# CPU.net
KiCad netlist of a schematic drawn in Altium Designer
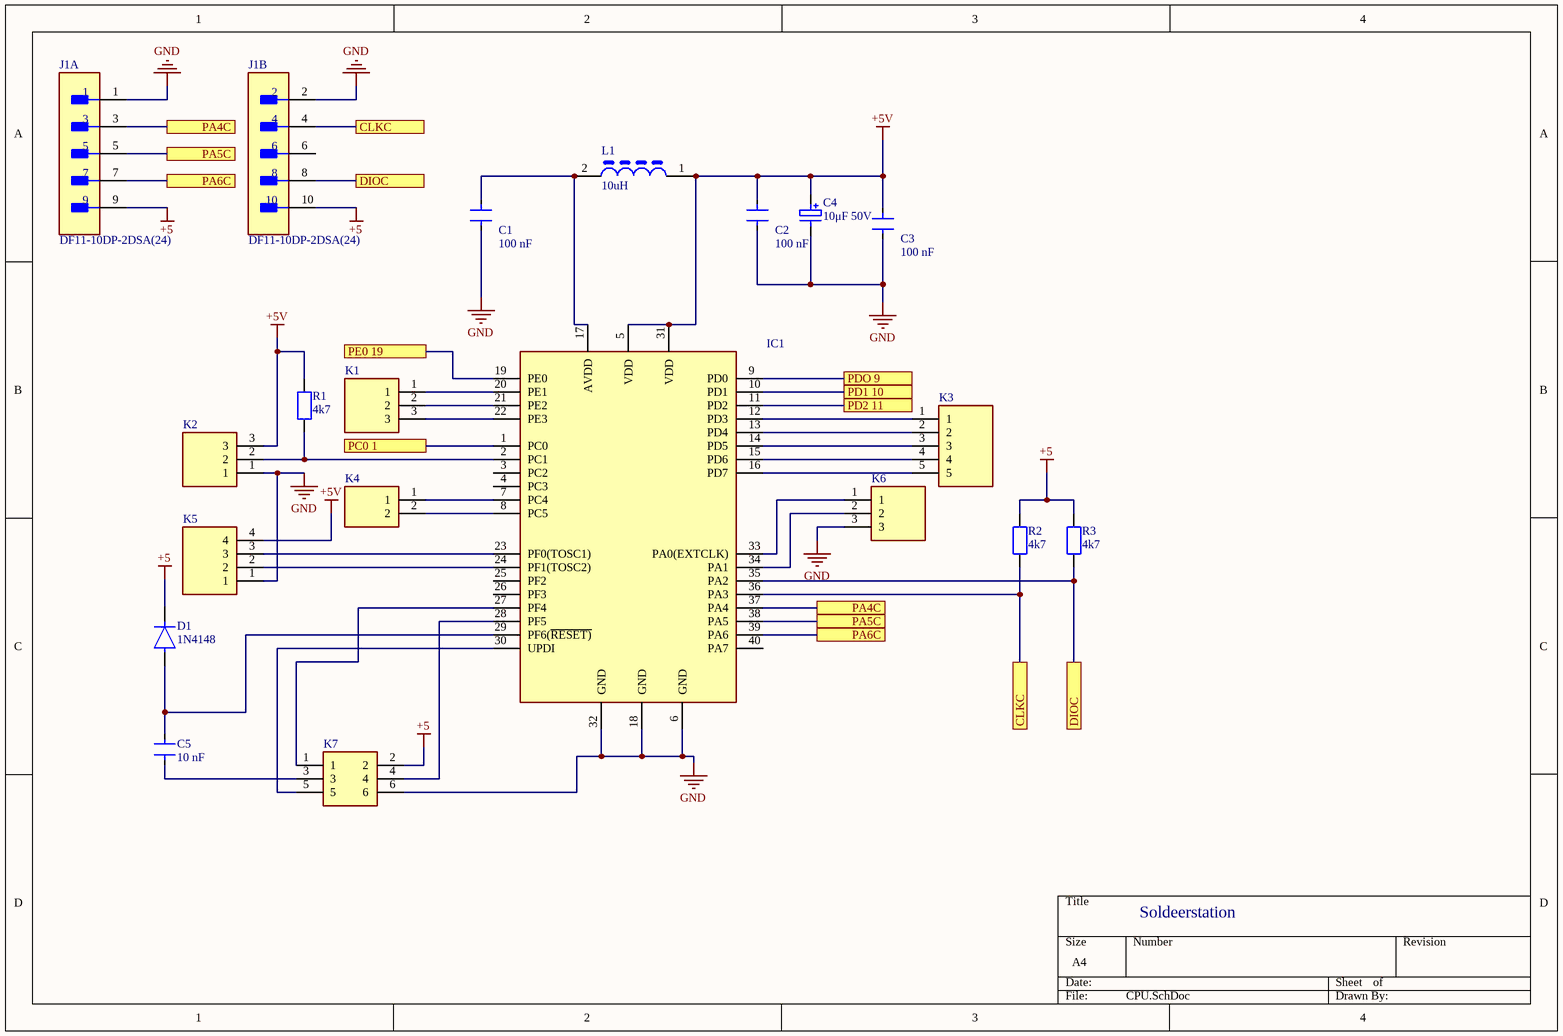
[diagram p0: CPU.SchDoc]

(export (version "E")
  (design (tool "Eeschema 10.0.6"))
  (components
    (comp (ref "C1")
      (value "100 nF")
      (footprint "0805")
      (description "Chip Multilayer Ceramic Capacitors for General Purpose, 0805, 10uF, X5R, 15%, 10%, 25V")
      (fields (field (name "VOLTAGE") "25V") (field (name "TOLERANCE") "10%"))
      (libsource (lib "Soldeerstation") (part "Condensator 0805"))
    )
    (comp (ref "C2")
      (value "100 nF")
      (footprint "0805")
      (description "Chip Multilayer Ceramic Capacitors for General Purpose, 0805, 10uF, X5R, 15%, 10%, 25V")
      (fields (field (name "VOLTAGE") "25V") (field (name "TOLERANCE") "10%"))
      (libsource (lib "Soldeerstation") (part "Condensator 0805"))
    )
    (comp (ref "C3")
      (value "100 nF")
      (footprint "0805")
      (description "Chip Multilayer Ceramic Capacitors for General Purpose, 0805, 10uF, X5R, 15%, 10%, 25V")
      (fields (field (name "VOLTAGE") "25V") (field (name "TOLERANCE") "10%"))
      (libsource (lib "Soldeerstation") (part "Condensator 0805"))
    )
    (comp (ref "C4")
      (value "10μF 50V")
      (footprint "Elco 10uF 50V")
      (fields
        (field (name "PART NUMBER") "02015A270JAT2A")
        (field (name "MANUFACTURER") "AVX Interconnect / Elco")
      )
      (libsource (lib "Soldeerstation") (part "Condensator Elco"))
    )
    (comp (ref "C5")
      (value "10 nF")
      (footprint "0805")
      (description "Chip Multilayer Ceramic Capacitors for General Purpose, 0805, 10uF, X5R, 15%, 10%, 25V")
      (fields (field (name "VOLTAGE") "25V") (field (name "TOLERANCE") "10%"))
      (libsource (lib "Soldeerstation") (part "Condensator 0805"))
    )
    (comp (ref "D1")
      (value "1N4148")
      (footprint "1N4148")
      (description "1N4148, 100 V, 200 mA, 4 ns")
      (fields (field (name "VOLTAGE") "100V"))
      (libsource (lib "Soldeerstation") (part "1N4148"))
    )
    (comp (ref "IC1")
      (value "ATMEGA4809-PF")
      (footprint "IC3")
      (description "ATmega4809-PF")
      (libsource (lib "Soldeerstation") (part "IC3"))
    )
    (comp (ref "J1")
      (value "DF11-10DP-2DSA(24)")
      (footprint "FP-DF11-10DP-2DSA_24-MFG")
      (description "CONN HEADER VERT 10POS 2MM")
      (fields
        (field (name "OCTOPART") "https://octopart.com/df11-10dp-2dsa%2824%29-hirose-39521433")
        (field (name "MANUFACTURER") "Hirose")
      )
      (libsource (lib "Soldeerstation") (part "CMP-11610-000008-1"))
    )
    (comp (ref "K1")
      (value "5-146280-3")
      (footprint "3 Pin Header")
      (description "Connector 5-146280-3")
      (fields (field (name "MOUSER2 PART NUMBER") "571-5-146280-3"))
      (libsource (lib "") (part "3 Pin Header_1"))
    )
    (comp (ref "K2")
      (value "5-146280-3")
      (footprint "3 Pin Header")
      (description "Connector 5-146280-3")
      (fields (field (name "MOUSER2 PART NUMBER") "571-5-146280-3"))
      (libsource (lib "") (part "3 Pin Header_2"))
    )
    (comp (ref "K3")
      (value "5-146280-5")
      (footprint "5 Pin Header")
      (description "Connector 5-146280-5")
      (fields (field (name "MOUSER2 PART NUMBER") "571-5-146280-5"))
      (libsource (lib "Soldeerstation") (part "5 Pin Header"))
    )
    (comp (ref "K4")
      (value "5-146280-2")
      (footprint "2 Pin Header")
      (description "Connector")
      (libsource (lib "Soldeerstation") (part "2 Pin Header"))
    )
    (comp (ref "K5")
      (value "5-146280-4")
      (footprint "4 Pin Header")
      (description "Connector 5-146280-4")
      (libsource (lib "Soldeerstation") (part "4 Pin Header"))
    )
    (comp (ref "K6")
      (value "5-146280-3")
      (footprint "3 Pin Header")
      (description "Connector 5-146280-3")
      (fields (field (name "MOUSER2 PART NUMBER") "571-5-146280-3"))
      (libsource (lib "Soldeerstation") (part "3 Pin Header"))
    )
    (comp (ref "K7")
      (value "2x3 Pin Header")
      (footprint "2x3 Pin Header")
      (description "Connector")
      (fields (field (name "MANUFACTURER_PART_NUMBER") "5-146256-3"))
      (libsource (lib "Soldeerstation") (part "2x3 Pin Header"))
    )
    (comp (ref "L1")
      (value "10uH")
      (footprint "Smoorspoel")
      (description "Inductor VLS6045EX-100M-H")
      (fields
        (field (name "MOUSER2 PART NUMBER") "810-VLS6045EX-100M-H")
        (field (name "MANUFACTURER_PART_NUMBER") "VLS6045EX-100M-H")
      )
      (libsource (lib "Soldeerstation") (part "Smoorspoel"))
    )
    (comp (ref "R1")
      (value "4k7")
      (footprint "Resistor")
      (description "Resistor")
      (fields (field (name "MANUFACTURER") "Vishay Dale") (field (name "PART NUMBER") "CRCW08050000Z0EA"))
      (libsource (lib "Soldeerstation") (part "Resistor"))
    )
    (comp (ref "R2")
      (value "4k7")
      (footprint "Resistor")
      (description "Resistor")
      (fields (field (name "MANUFACTURER") "Vishay Dale") (field (name "PART NUMBER") "CRCW08050000Z0EA"))
      (libsource (lib "Soldeerstation") (part "Resistor"))
    )
    (comp (ref "R3")
      (value "4k7")
      (footprint "Resistor")
      (description "Resistor")
      (fields (field (name "MANUFACTURER") "Vishay Dale") (field (name "PART NUMBER") "CRCW08050000Z0EA"))
      (libsource (lib "Soldeerstation") (part "Resistor"))
    )
  )
  (nets
    (net (code "1") (name "+5") (class "Default")
      (node (ref "D1") (pin "1") (pinfunction "C_1") (pintype "passive"))
      (node (ref "J1") (pin "10") (pinfunction "10_10") (pintype "passive"))
      (node (ref "J1") (pin "9") (pinfunction "9_9") (pintype "passive"))
      (node (ref "K7") (pin "2") (pinfunction "2_2") (pintype "passive"))
      (node (ref "R2") (pin "2") (pinfunction "2_2") (pintype "passive"))
      (node (ref "R3") (pin "2") (pinfunction "2_2") (pintype "passive"))
    )
    (net (code "2") (name "+5V") (class "Default")
      (node (ref "C2") (pin "1") (pinfunction "1_1") (pintype "passive"))
      (node (ref "C3") (pin "1") (pinfunction "1_1") (pintype "passive"))
      (node (ref "C4") (pin "1") (pinfunction "1_1") (pintype "passive"))
      (node (ref "IC1") (pin "31") (pinfunction "VDD_31") (pintype "power_in"))
      (node (ref "IC1") (pin "5") (pinfunction "VDD_5") (pintype "power_in"))
      (node (ref "K2") (pin "3") (pinfunction "3_3") (pintype "passive"))
      (node (ref "K5") (pin "4") (pinfunction "4_4") (pintype "passive"))
      (node (ref "L1") (pin "1") (pinfunction "1_1") (pintype "passive"))
      (node (ref "R1") (pin "2") (pinfunction "2_2") (pintype "passive"))
    )
    (net (code "3") (name "/CLKC") (class "Default")
      (node (ref "IC1") (pin "36") (pinfunction "PA3_36") (pintype "power_in"))
      (node (ref "J1") (pin "4") (pinfunction "4_4") (pintype "passive"))
      (node (ref "R2") (pin "1") (pintype "passive"))
    )
    (net (code "4") (name "/DIOC") (class "Default")
      (node (ref "IC1") (pin "35") (pinfunction "PA2_35") (pintype "power_in"))
      (node (ref "J1") (pin "8") (pinfunction "8_8") (pintype "passive"))
      (node (ref "R3") (pin "1") (pintype "passive"))
    )
    (net (code "5") (name "/PA4C") (class "Default")
      (node (ref "IC1") (pin "37") (pinfunction "PA4_37") (pintype "power_in"))
      (node (ref "J1") (pin "3") (pinfunction "3_3") (pintype "passive"))
    )
    (net (code "6") (name "/PA5C") (class "Default")
      (node (ref "IC1") (pin "38") (pinfunction "PA5_38") (pintype "power_in"))
      (node (ref "J1") (pin "5") (pinfunction "5_5") (pintype "passive"))
    )
    (net (code "7") (name "/PA6C") (class "Default")
      (node (ref "IC1") (pin "39") (pinfunction "PA6_39") (pintype "power_in"))
      (node (ref "J1") (pin "7") (pinfunction "7_7") (pintype "passive"))
    )
    (net (code "8") (name "/PC0 1") (class "Default")
      (node (ref "IC1") (pin "1") (pinfunction "PC0_1") (pintype "passive"))
    )
    (net (code "9") (name "/PD1 10") (class "Default")
      (node (ref "IC1") (pin "10") (pinfunction "PD1_10") (pintype "power_in"))
    )
    (net (code "10") (name "/PD2 11") (class "Default")
      (node (ref "IC1") (pin "11") (pinfunction "PD2_11") (pintype "power_in"))
    )
    (net (code "11") (name "/PDO 9") (class "Default")
      (node (ref "IC1") (pin "9") (pinfunction "PD0_9") (pintype "power_in"))
    )
    (net (code "12") (name "/PE0 19") (class "Default")
      (node (ref "IC1") (pin "19") (pinfunction "PE0_19") (pintype "passive"))
    )
    (net (code "13") (name "GND") (class "Default")
      (node (ref "C1") (pin "2") (pinfunction "2_2") (pintype "passive"))
      (node (ref "C2") (pin "2") (pinfunction "2_2") (pintype "passive"))
      (node (ref "C3") (pin "2") (pinfunction "2_2") (pintype "passive"))
      (node (ref "C4") (pin "2") (pinfunction "2_2") (pintype "passive"))
      (node (ref "IC1") (pin "18") (pinfunction "GND_18") (pintype "power_in"))
      (node (ref "IC1") (pin "32") (pinfunction "GND_32") (pintype "power_in"))
      (node (ref "IC1") (pin "6") (pinfunction "GND_6") (pintype "power_in"))
      (node (ref "J1") (pin "1") (pinfunction "1_1") (pintype "passive"))
      (node (ref "J1") (pin "2") (pinfunction "2_2") (pintype "passive"))
      (node (ref "K2") (pin "1") (pinfunction "1_1") (pintype "passive"))
      (node (ref "K5") (pin "1") (pinfunction "1_1") (pintype "passive"))
      (node (ref "K6") (pin "3") (pinfunction "3_3") (pintype "passive"))
      (node (ref "K7") (pin "6") (pinfunction "6_6") (pintype "passive"))
    )
    (net (code "14") (name "Net-(C5-Pad1)") (class "Default")
      (node (ref "C5") (pin "1") (pinfunction "1_1") (pintype "passive"))
      (node (ref "K7") (pin "3") (pinfunction "3_3") (pintype "passive"))
    )
    (net (code "15") (name "Net-(D1-A)") (class "Default")
      (node (ref "C5") (pin "2") (pinfunction "2_2") (pintype "passive"))
      (node (ref "D1") (pin "2") (pinfunction "A_2") (pintype "passive"))
      (node (ref "IC1") (pin "29") (pinfunction "PF6(~{RESET)}_29") (pintype "passive"))
    )
    (net (code "16") (name "Net-(IC1-AVDD)") (class "Default")
      (node (ref "C1") (pin "1") (pinfunction "1_1") (pintype "passive"))
      (node (ref "IC1") (pin "17") (pinfunction "AVDD_17") (pintype "power_in"))
      (node (ref "L1") (pin "2") (pinfunction "2_2") (pintype "passive"))
    )
    (net (code "17") (name "Net-(IC1-PA0(EXTCLK))") (class "Default")
      (node (ref "IC1") (pin "33") (pinfunction "PA0(EXTCLK)_33") (pintype "power_in"))
      (node (ref "K6") (pin "1") (pinfunction "1_1") (pintype "passive"))
    )
    (net (code "18") (name "Net-(IC1-PA1)") (class "Default")
      (node (ref "IC1") (pin "34") (pinfunction "PA1_34") (pintype "power_in"))
      (node (ref "K6") (pin "2") (pinfunction "2_2") (pintype "passive"))
    )
    (net (code "19") (name "Net-(IC1-PC1)") (class "Default")
      (node (ref "IC1") (pin "2") (pinfunction "PC1_2") (pintype "passive"))
      (node (ref "K2") (pin "2") (pinfunction "2_2") (pintype "passive"))
      (node (ref "R1") (pin "1") (pintype "passive"))
    )
    (net (code "20") (name "Net-(IC1-PC4)") (class "Default")
      (node (ref "IC1") (pin "7") (pinfunction "PC4_7") (pintype "passive"))
      (node (ref "K4") (pin "1") (pinfunction "1_1") (pintype "passive"))
    )
    (net (code "21") (name "Net-(IC1-PC5)") (class "Default")
      (node (ref "IC1") (pin "8") (pinfunction "PC5_8") (pintype "passive"))
      (node (ref "K4") (pin "2") (pinfunction "2_2") (pintype "passive"))
    )
    (net (code "22") (name "Net-(IC1-PD3)") (class "Default")
      (node (ref "IC1") (pin "12") (pinfunction "PD3_12") (pintype "power_in"))
      (node (ref "K3") (pin "1") (pinfunction "1_1") (pintype "passive"))
    )
    (net (code "23") (name "Net-(IC1-PD4)") (class "Default")
      (node (ref "IC1") (pin "13") (pinfunction "PD4_13") (pintype "power_in"))
      (node (ref "K3") (pin "2") (pinfunction "2_2") (pintype "passive"))
    )
    (net (code "24") (name "Net-(IC1-PD5)") (class "Default")
      (node (ref "IC1") (pin "14") (pinfunction "PD5_14") (pintype "power_in"))
      (node (ref "K3") (pin "3") (pinfunction "3_3") (pintype "passive"))
    )
    (net (code "25") (name "Net-(IC1-PD6)") (class "Default")
      (node (ref "IC1") (pin "15") (pinfunction "PD6_15") (pintype "power_in"))
      (node (ref "K3") (pin "4") (pinfunction "4_4") (pintype "passive"))
    )
    (net (code "26") (name "Net-(IC1-PD7)") (class "Default")
      (node (ref "IC1") (pin "16") (pinfunction "PD7_16") (pintype "power_in"))
      (node (ref "K3") (pin "5") (pinfunction "5_5") (pintype "passive"))
    )
    (net (code "27") (name "Net-(IC1-PE1)") (class "Default")
      (node (ref "IC1") (pin "20") (pinfunction "PE1_20") (pintype "power_in"))
      (node (ref "K1") (pin "1") (pinfunction "1_1") (pintype "passive"))
    )
    (net (code "28") (name "Net-(IC1-PE2)") (class "Default")
      (node (ref "IC1") (pin "21") (pinfunction "PE2_21") (pintype "passive"))
      (node (ref "K1") (pin "2") (pinfunction "2_2") (pintype "passive"))
    )
    (net (code "29") (name "Net-(IC1-PE3)") (class "Default")
      (node (ref "IC1") (pin "22") (pinfunction "PE3_22") (pintype "passive"))
      (node (ref "K1") (pin "3") (pinfunction "3_3") (pintype "passive"))
    )
    (net (code "30") (name "Net-(IC1-PF0(TOSC1))") (class "Default")
      (node (ref "IC1") (pin "23") (pinfunction "PF0(TOSC1)_23") (pintype "passive"))
      (node (ref "K5") (pin "3") (pinfunction "3_3") (pintype "passive"))
    )
    (net (code "31") (name "Net-(IC1-PF1(TOSC2))") (class "Default")
      (node (ref "IC1") (pin "24") (pinfunction "PF1(TOSC2)_24") (pintype "passive"))
      (node (ref "K5") (pin "2") (pinfunction "2_2") (pintype "passive"))
    )
    (net (code "32") (name "Net-(IC1-PF4)") (class "Default")
      (node (ref "IC1") (pin "27") (pinfunction "PF4_27") (pintype "passive"))
      (node (ref "K7") (pin "1") (pinfunction "1_1") (pintype "passive"))
    )
    (net (code "33") (name "Net-(IC1-PF5)") (class "Default")
      (node (ref "IC1") (pin "28") (pinfunction "PF5_28") (pintype "passive"))
      (node (ref "K7") (pin "4") (pinfunction "4_4") (pintype "passive"))
    )
    (net (code "34") (name "Net-(IC1-UPDI)") (class "Default")
      (node (ref "IC1") (pin "30") (pinfunction "UPDI_30") (pintype "passive"))
      (node (ref "K7") (pin "5") (pinfunction "5_5") (pintype "passive"))
    )
    (net (code "35") (name "unconnected-(IC1-PA7-Pad40)") (class "Default")
      (node (ref "IC1") (pin "40") (pinfunction "PA7_40") (pintype "power_in"))
    )
    (net (code "36") (name "unconnected-(IC1-PC2-Pad3)") (class "Default")
      (node (ref "IC1") (pin "3") (pinfunction "PC2_3") (pintype "passive"))
    )
    (net (code "37") (name "unconnected-(IC1-PC3-Pad4)") (class "Default")
      (node (ref "IC1") (pin "4") (pinfunction "PC3_4") (pintype "passive"))
    )
    (net (code "38") (name "unconnected-(IC1-PF2-Pad25)") (class "Default")
      (node (ref "IC1") (pin "25") (pinfunction "PF2_25") (pintype "passive"))
    )
    (net (code "39") (name "unconnected-(IC1-PF3-Pad26)") (class "Default")
      (node (ref "IC1") (pin "26") (pinfunction "PF3_26") (pintype "passive"))
    )
    (net (code "40") (name "unconnected-(J1-Pad6)") (class "Default")
      (node (ref "J1") (pin "6") (pinfunction "6_6") (pintype "passive"))
    )
  )
)
